# erleuchtung.net
KiCad netlist of a schematic drawn in EAGLE
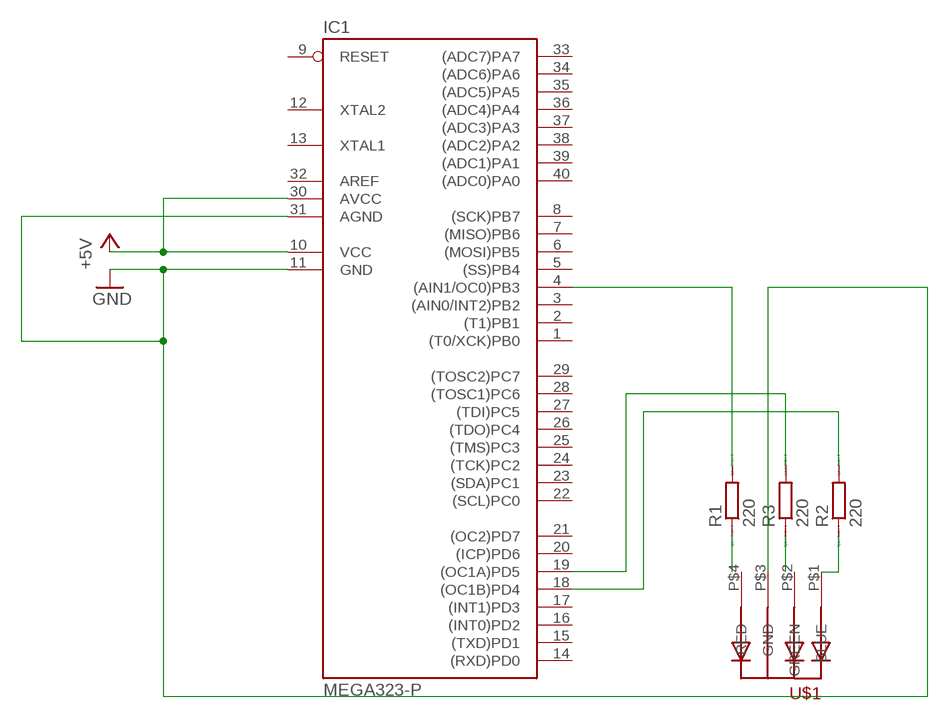
[diagram p0: schematic, sheet 1]

(export (version "E")
  (design (tool "Eeschema 10.0.6"))
  (components
    (comp (ref "IC1")
      (value "MEGA323-P")
      (footprint "eagle-import:DIL40")
      (libsource (lib "eagle-import") (part "MEGA323-P"))
    )
    (comp (ref "R1")
      (value "220")
      (footprint "eagle-import:0207_5V")
      (libsource (lib "eagle-import") (part "R-EU_0207_5V"))
    )
    (comp (ref "R2")
      (value "220")
      (footprint "eagle-import:0207_5V")
      (libsource (lib "eagle-import") (part "R-EU_0207_5V"))
    )
    (comp (ref "R3")
      (value "220")
      (footprint "eagle-import:0207_5V")
      (libsource (lib "eagle-import") (part "R-EU_0207_5V"))
    )
    (comp (ref "U$1")
      (value "5MMRGBLED")
      (footprint "eagle-import:LED5MMRGB")
      (libsource (lib "eagle-import") (part "5MMRGBLED"))
    )
  )
  (nets
    (net (code "1") (name "+5V") (class "Default")
      (node (ref "IC1") (pin "10") (pinfunction "VCC_10") (pintype "power_in"))
      (node (ref "IC1") (pin "30") (pinfunction "AVCC_30") (pintype "power_in"))
    )
    (net (code "2") (name "GND") (class "Default")
      (node (ref "IC1") (pin "11") (pinfunction "GND_11") (pintype "power_in"))
      (node (ref "IC1") (pin "31") (pinfunction "AGND_31") (pintype "power_in"))
      (node (ref "U$1") (pin "P$3") (pinfunction "GND_P$3") (pintype "bidirectional"))
    )
    (net (code "3") (name "Net-(IC1-(AIN1{slash}OC0)PB3)") (class "Default")
      (node (ref "IC1") (pin "4") (pinfunction "(AIN1/OC0)PB3_4") (pintype "bidirectional"))
      (node (ref "R1") (pin "2") (pinfunction "2_2") (pintype "passive"))
    )
    (net (code "4") (name "Net-(IC1-(OC1A)PD5)") (class "Default")
      (node (ref "IC1") (pin "19") (pinfunction "(OC1A)PD5_19") (pintype "bidirectional"))
      (node (ref "R3") (pin "2") (pinfunction "2_2") (pintype "passive"))
    )
    (net (code "5") (name "Net-(IC1-(OC1B)PD4)") (class "Default")
      (node (ref "IC1") (pin "18") (pinfunction "(OC1B)PD4_18") (pintype "bidirectional"))
      (node (ref "R2") (pin "2") (pinfunction "2_2") (pintype "passive"))
    )
    (net (code "6") (name "Net-(U$1-BLUE)") (class "Default")
      (node (ref "R2") (pin "1") (pinfunction "1_1") (pintype "passive"))
      (node (ref "U$1") (pin "P$1") (pinfunction "BLUE_P$1") (pintype "bidirectional"))
    )
    (net (code "7") (name "unconnected-(IC1-(ADC0)PA0-Pad40)") (class "Default")
      (node (ref "IC1") (pin "40") (pinfunction "(ADC0)PA0_40") (pintype "bidirectional"))
    )
    (net (code "8") (name "unconnected-(IC1-(ADC1)PA1-Pad39)") (class "Default")
      (node (ref "IC1") (pin "39") (pinfunction "(ADC1)PA1_39") (pintype "bidirectional"))
    )
    (net (code "9") (name "unconnected-(IC1-(ADC2)PA2-Pad38)") (class "Default")
      (node (ref "IC1") (pin "38") (pinfunction "(ADC2)PA2_38") (pintype "bidirectional"))
    )
    (net (code "10") (name "unconnected-(IC1-(ADC3)PA3-Pad37)") (class "Default")
      (node (ref "IC1") (pin "37") (pinfunction "(ADC3)PA3_37") (pintype "bidirectional"))
    )
    (net (code "11") (name "unconnected-(IC1-(ADC4)PA4-Pad36)") (class "Default")
      (node (ref "IC1") (pin "36") (pinfunction "(ADC4)PA4_36") (pintype "bidirectional"))
    )
    (net (code "12") (name "unconnected-(IC1-(ADC5)PA5-Pad35)") (class "Default")
      (node (ref "IC1") (pin "35") (pinfunction "(ADC5)PA5_35") (pintype "bidirectional"))
    )
    (net (code "13") (name "unconnected-(IC1-(ADC6)PA6-Pad34)") (class "Default")
      (node (ref "IC1") (pin "34") (pinfunction "(ADC6)PA6_34") (pintype "bidirectional"))
    )
    (net (code "14") (name "unconnected-(IC1-(ADC7)PA7-Pad33)") (class "Default")
      (node (ref "IC1") (pin "33") (pinfunction "(ADC7)PA7_33") (pintype "bidirectional"))
    )
    (net (code "15") (name "unconnected-(IC1-(AIN0{slash}INT2)PB2-Pad3)") (class "Default")
      (node (ref "IC1") (pin "3") (pinfunction "(AIN0/INT2)PB2_3") (pintype "bidirectional"))
    )
    (net (code "16") (name "unconnected-(IC1-(ICP)PD6-Pad20)") (class "Default")
      (node (ref "IC1") (pin "20") (pinfunction "(ICP)PD6_20") (pintype "bidirectional"))
    )
    (net (code "17") (name "unconnected-(IC1-(INT0)PD2-Pad16)") (class "Default")
      (node (ref "IC1") (pin "16") (pinfunction "(INT0)PD2_16") (pintype "bidirectional"))
    )
    (net (code "18") (name "unconnected-(IC1-(INT1)PD3-Pad17)") (class "Default")
      (node (ref "IC1") (pin "17") (pinfunction "(INT1)PD3_17") (pintype "bidirectional"))
    )
    (net (code "19") (name "unconnected-(IC1-(MISO)PB6-Pad7)") (class "Default")
      (node (ref "IC1") (pin "7") (pinfunction "(MISO)PB6_7") (pintype "bidirectional"))
    )
    (net (code "20") (name "unconnected-(IC1-(MOSI)PB5-Pad6)") (class "Default")
      (node (ref "IC1") (pin "6") (pinfunction "(MOSI)PB5_6") (pintype "bidirectional"))
    )
    (net (code "21") (name "unconnected-(IC1-(OC2)PD7-Pad21)") (class "Default")
      (node (ref "IC1") (pin "21") (pinfunction "(OC2)PD7_21") (pintype "bidirectional"))
    )
    (net (code "22") (name "unconnected-(IC1-(RXD)PD0-Pad14)") (class "Default")
      (node (ref "IC1") (pin "14") (pinfunction "(RXD)PD0_14") (pintype "bidirectional"))
    )
    (net (code "23") (name "unconnected-(IC1-(SCK)PB7-Pad8)") (class "Default")
      (node (ref "IC1") (pin "8") (pinfunction "(SCK)PB7_8") (pintype "bidirectional"))
    )
    (net (code "24") (name "unconnected-(IC1-(SCL)PC0-Pad22)") (class "Default")
      (node (ref "IC1") (pin "22") (pinfunction "(SCL)PC0_22") (pintype "bidirectional"))
    )
    (net (code "25") (name "unconnected-(IC1-(SDA)PC1-Pad23)") (class "Default")
      (node (ref "IC1") (pin "23") (pinfunction "(SDA)PC1_23") (pintype "bidirectional"))
    )
    (net (code "26") (name "unconnected-(IC1-(SS)PB4-Pad5)") (class "Default")
      (node (ref "IC1") (pin "5") (pinfunction "(SS)PB4_5") (pintype "bidirectional"))
    )
    (net (code "27") (name "unconnected-(IC1-(T0{slash}XCK)PB0-Pad1)") (class "Default")
      (node (ref "IC1") (pin "1") (pinfunction "(T0/XCK)PB0_1") (pintype "bidirectional"))
    )
    (net (code "28") (name "unconnected-(IC1-(T1)PB1-Pad2)") (class "Default")
      (node (ref "IC1") (pin "2") (pinfunction "(T1)PB1_2") (pintype "bidirectional"))
    )
    (net (code "29") (name "unconnected-(IC1-(TCK)PC2-Pad24)") (class "Default")
      (node (ref "IC1") (pin "24") (pinfunction "(TCK)PC2_24") (pintype "bidirectional"))
    )
    (net (code "30") (name "unconnected-(IC1-(TDI)PC5-Pad27)") (class "Default")
      (node (ref "IC1") (pin "27") (pinfunction "(TDI)PC5_27") (pintype "bidirectional"))
    )
    (net (code "31") (name "unconnected-(IC1-(TDO)PC4-Pad26)") (class "Default")
      (node (ref "IC1") (pin "26") (pinfunction "(TDO)PC4_26") (pintype "bidirectional"))
    )
    (net (code "32") (name "unconnected-(IC1-(TMS)PC3-Pad25)") (class "Default")
      (node (ref "IC1") (pin "25") (pinfunction "(TMS)PC3_25") (pintype "bidirectional"))
    )
    (net (code "33") (name "unconnected-(IC1-(TOSC1)PC6-Pad28)") (class "Default")
      (node (ref "IC1") (pin "28") (pinfunction "(TOSC1)PC6_28") (pintype "bidirectional"))
    )
    (net (code "34") (name "unconnected-(IC1-(TOSC2)PC7-Pad29)") (class "Default")
      (node (ref "IC1") (pin "29") (pinfunction "(TOSC2)PC7_29") (pintype "bidirectional"))
    )
    (net (code "35") (name "unconnected-(IC1-(TXD)PD1-Pad15)") (class "Default")
      (node (ref "IC1") (pin "15") (pinfunction "(TXD)PD1_15") (pintype "bidirectional"))
    )
    (net (code "36") (name "unconnected-(IC1-AREF-Pad32)") (class "Default")
      (node (ref "IC1") (pin "32") (pinfunction "AREF_32") (pintype "passive"))
    )
    (net (code "37") (name "unconnected-(IC1-RESET-Pad9)") (class "Default")
      (node (ref "IC1") (pin "9") (pinfunction "RESET_9") (pintype "input"))
    )
    (net (code "38") (name "unconnected-(IC1-XTAL1-Pad13)") (class "Default")
      (node (ref "IC1") (pin "13") (pinfunction "XTAL1_13") (pintype "bidirectional"))
    )
    (net (code "39") (name "unconnected-(IC1-XTAL2-Pad12)") (class "Default")
      (node (ref "IC1") (pin "12") (pinfunction "XTAL2_12") (pintype "bidirectional"))
    )
    (net (code "40") (name "unconnected-(R1-Pad1)") (class "Default")
      (node (ref "R1") (pin "1") (pinfunction "1_1") (pintype "passive"))
    )
    (net (code "41") (name "unconnected-(R3-Pad1)") (class "Default")
      (node (ref "R3") (pin "1") (pinfunction "1_1") (pintype "passive"))
    )
    (net (code "42") (name "unconnected-(U$1-GREEN-PadP$2)") (class "Default")
      (node (ref "U$1") (pin "P$2") (pinfunction "GREEN_P$2") (pintype "bidirectional"))
    )
    (net (code "43") (name "unconnected-(U$1-RED-PadP$4)") (class "Default")
      (node (ref "U$1") (pin "P$4") (pinfunction "RED_P$4") (pintype "bidirectional"))
    )
  )
)
